# Op-amp_Microphone_Preamp_single-supply.net
KiCad netlist of a schematic drawn in EAGLE
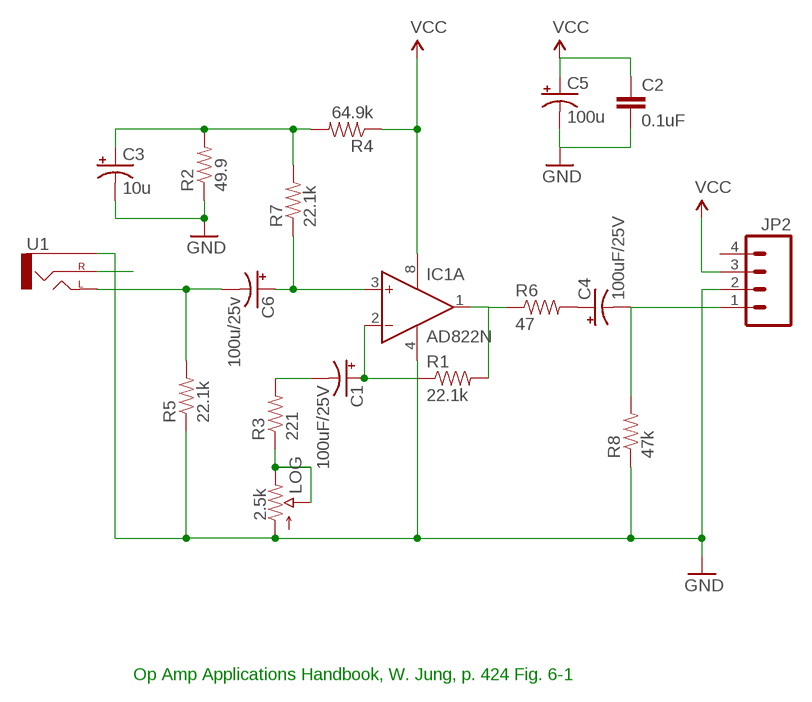
[diagram p0: schematic, sheet 1]

(export (version "E")
  (design (tool "Eeschema 10.0.6"))
  (components
    (comp (ref "C1")
      (value "100uF/25V")
      (footprint "eagle-import:CPOL-RADIAL-100UF-25V")
      (libsource (lib "eagle-import") (part "CAP_POLPTH1"))
    )
    (comp (ref "C2")
      (value "0.1uF")
      (footprint "eagle-import:CAP-PTH-SMALL-KIT")
      (libsource (lib "eagle-import") (part "CAPKIT"))
    )
    (comp (ref "C3")
      (value "10u")
      (footprint "eagle-import:CPOL-RADIAL-100UF-25V")
      (libsource (lib "eagle-import") (part "CAP_POLPTH1"))
    )
    (comp (ref "C4")
      (value "100uF/25V")
      (footprint "eagle-import:CPOL-RADIAL-100UF-25V")
      (libsource (lib "eagle-import") (part "CAP_POLPTH1"))
    )
    (comp (ref "C5")
      (value "100u")
      (footprint "eagle-import:CPOL-RADIAL-100UF-25V")
      (libsource (lib "eagle-import") (part "CAP_POLPTH1"))
    )
    (comp (ref "C6")
      (value "100u/25v")
      (footprint "eagle-import:CPOL-RADIAL-100UF-25V")
      (libsource (lib "eagle-import") (part "CAP_POLPTH1"))
    )
    (comp (ref "IC1")
      (value "AD822N")
      (footprint "eagle-import:DIL08")
      (libsource (lib "eagle-import") (part "AD822N"))
    )
    (comp (ref "JP2")
      (value "M04POLAR")
      (footprint "eagle-import:MOLEX-1X4")
      (libsource (lib "eagle-import") (part "M04POLAR"))
    )
    (comp (ref "LOG")
      (value "2.5k")
      (footprint "eagle-import:POT_ALPHA_RV16AF-20")
      (libsource (lib "eagle-import") (part "POT-RV16AF-20"))
    )
    (comp (ref "R1")
      (value "22.1k")
      (footprint "eagle-import:1_6W-RES")
      (libsource (lib "eagle-import") (part "RESISTORPTH-1/6W"))
    )
    (comp (ref "R2")
      (value "49.9")
      (footprint "eagle-import:1_6W-RES")
      (libsource (lib "eagle-import") (part "RESISTORPTH-1/6W"))
    )
    (comp (ref "R3")
      (value "221")
      (footprint "eagle-import:1_6W-RES")
      (libsource (lib "eagle-import") (part "RESISTORPTH-1/6W"))
    )
    (comp (ref "R4")
      (value "64.9k")
      (footprint "eagle-import:1_6W-RES")
      (libsource (lib "eagle-import") (part "RESISTORPTH-1/6W"))
    )
    (comp (ref "R5")
      (value "22.1k")
      (footprint "eagle-import:1_6W-RES")
      (libsource (lib "eagle-import") (part "RESISTORPTH-1/6W"))
    )
    (comp (ref "R6")
      (value "47")
      (footprint "eagle-import:1_6W-RES")
      (libsource (lib "eagle-import") (part "RESISTORPTH-1/6W"))
    )
    (comp (ref "R7")
      (value "22.1k")
      (footprint "eagle-import:1_6W-RES")
      (libsource (lib "eagle-import") (part "RESISTORPTH-1/6W"))
    )
    (comp (ref "R8")
      (value "47k")
      (footprint "eagle-import:1_6W-RES")
      (libsource (lib "eagle-import") (part "RESISTORPTH-1/6W"))
    )
    (comp (ref "U1")
      (value "AUDIO-JACKPTH")
      (footprint "eagle-import:AUDIO-JACK")
      (libsource (lib "eagle-import") (part "AUDIO-JACKPTH"))
    )
  )
  (nets
    (net (code "1") (name "GND") (class "Default")
      (node (ref "C2") (pin "2") (pinfunction "2_2") (pintype "passive"))
      (node (ref "C3") (pin "2") (pinfunction "-_2") (pintype "passive"))
      (node (ref "C5") (pin "2") (pinfunction "-_2") (pintype "passive"))
      (node (ref "IC1") (pin "4") (pinfunction "V-_4") (pintype "power_in"))
      (node (ref "JP2") (pin "2") (pinfunction "2_2") (pintype "passive"))
      (node (ref "LOG") (pin "1") (pinfunction "A_1") (pintype "passive"))
      (node (ref "R2") (pin "1") (pinfunction "1_1") (pintype "passive"))
      (node (ref "R5") (pin "1") (pinfunction "1_1") (pintype "passive"))
      (node (ref "R8") (pin "1") (pinfunction "1_1") (pintype "passive"))
      (node (ref "U1") (pin "SLEEVE") (pinfunction "SLEEVE_SLEEVE") (pintype "bidirectional"))
    )
    (net (code "2") (name "Net-(C1-+)") (class "Default")
      (node (ref "C1") (pin "1") (pinfunction "+_1") (pintype "passive"))
      (node (ref "IC1") (pin "2") (pinfunction "IN-_2") (pintype "input"))
      (node (ref "R1") (pin "1") (pinfunction "1_1") (pintype "passive"))
    )
    (net (code "3") (name "Net-(C1--)") (class "Default")
      (node (ref "C1") (pin "2") (pinfunction "-_2") (pintype "passive"))
      (node (ref "R3") (pin "2") (pinfunction "2_2") (pintype "passive"))
    )
    (net (code "4") (name "Net-(C3-+)") (class "Default")
      (node (ref "C3") (pin "1") (pinfunction "+_1") (pintype "passive"))
      (node (ref "R2") (pin "2") (pinfunction "2_2") (pintype "passive"))
      (node (ref "R4") (pin "2") (pinfunction "2_2") (pintype "passive"))
      (node (ref "R7") (pin "2") (pinfunction "2_2") (pintype "passive"))
    )
    (net (code "5") (name "Net-(C4-+)") (class "Default")
      (node (ref "C4") (pin "1") (pinfunction "+_1") (pintype "passive"))
      (node (ref "R6") (pin "2") (pinfunction "2_2") (pintype "passive"))
    )
    (net (code "6") (name "Net-(C4--)") (class "Default")
      (node (ref "C4") (pin "2") (pinfunction "-_2") (pintype "passive"))
      (node (ref "JP2") (pin "1") (pinfunction "1_1") (pintype "passive"))
      (node (ref "R8") (pin "2") (pinfunction "2_2") (pintype "passive"))
    )
    (net (code "7") (name "Net-(C6-+)") (class "Default")
      (node (ref "C6") (pin "1") (pinfunction "+_1") (pintype "passive"))
      (node (ref "IC1") (pin "3") (pinfunction "IN+_3") (pintype "input"))
      (node (ref "R7") (pin "1") (pinfunction "1_1") (pintype "passive"))
    )
    (net (code "8") (name "Net-(C6--)") (class "Default")
      (node (ref "C6") (pin "2") (pinfunction "-_2") (pintype "passive"))
      (node (ref "R5") (pin "2") (pinfunction "2_2") (pintype "passive"))
      (node (ref "U1") (pin "TIP") (pinfunction "LEFT_TIP") (pintype "bidirectional"))
    )
    (net (code "9") (name "Net-(IC1A-OUT)") (class "Default")
      (node (ref "IC1") (pin "1") (pinfunction "OUT_1") (pintype "output"))
      (node (ref "R1") (pin "2") (pinfunction "2_2") (pintype "passive"))
      (node (ref "R6") (pin "1") (pinfunction "1_1") (pintype "passive"))
    )
    (net (code "10") (name "Net-(LOG-E)") (class "Default")
      (node (ref "LOG") (pin "2") (pinfunction "S_2") (pintype "passive"))
      (node (ref "LOG") (pin "3") (pinfunction "E_3") (pintype "passive"))
      (node (ref "R3") (pin "1") (pinfunction "1_1") (pintype "passive"))
    )
    (net (code "11") (name "VCC") (class "Default")
      (node (ref "C2") (pin "1") (pinfunction "1_1") (pintype "passive"))
      (node (ref "C5") (pin "1") (pinfunction "+_1") (pintype "passive"))
      (node (ref "IC1") (pin "8") (pinfunction "V+_8") (pintype "power_in"))
      (node (ref "JP2") (pin "3") (pinfunction "3_3") (pintype "passive"))
      (node (ref "R4") (pin "1") (pinfunction "1_1") (pintype "passive"))
    )
    (net (code "12") (name "unconnected-(JP2-Pad4)") (class "Default")
      (node (ref "JP2") (pin "4") (pinfunction "4_4") (pintype "passive"))
    )
    (net (code "13") (name "unconnected-(U1-RIGHT-PadRING)") (class "Default")
      (node (ref "U1") (pin "RING") (pinfunction "RIGHT_RING") (pintype "bidirectional"))
    )
  )
)
